# 1_SCH_RP2040.net
KiCad netlist of a schematic drawn in Altium Designer
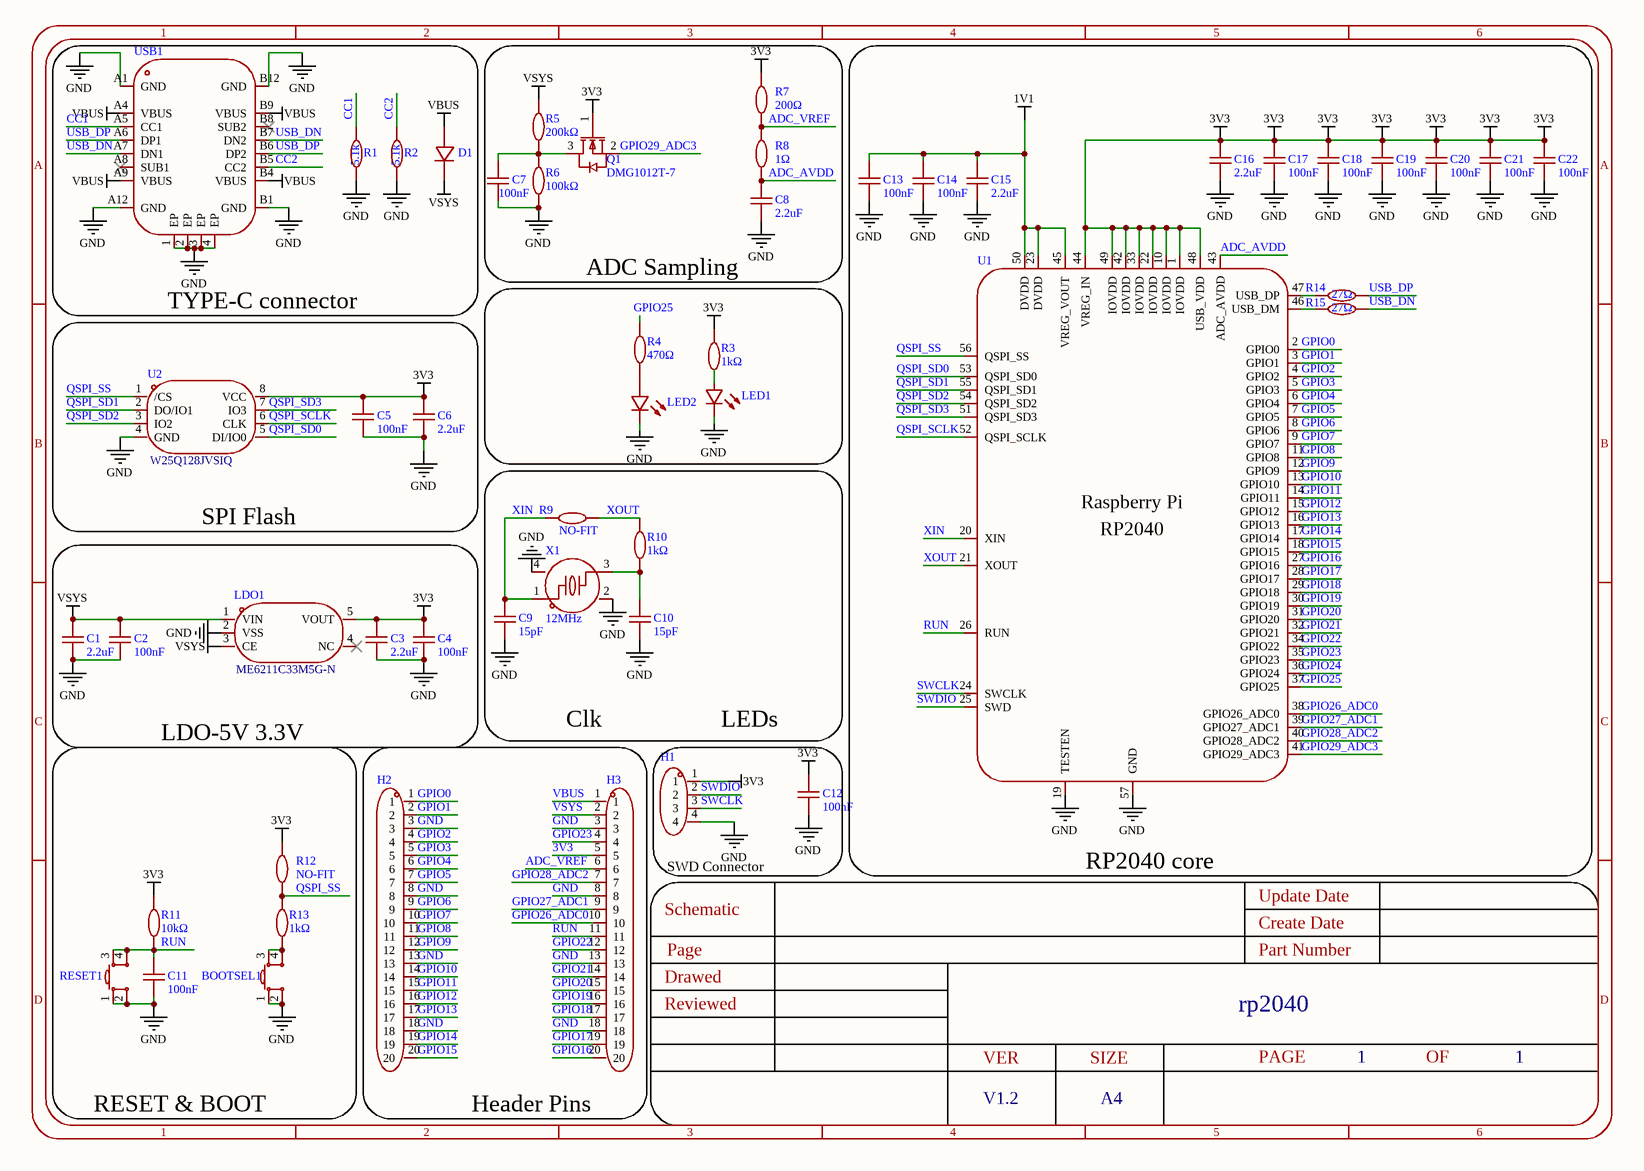
[diagram p0: 1_SCH_RP2040.schdoc]

(export (version "E")
  (design (tool "Eeschema 10.0.6"))
  (components
    (comp (ref "BOOTSEL1")
      (value "PTS815SJK250SMTRLFS")
      (footprint "SW-SMD_4P-L4.2-W3.3-P2.15-LS5.1")
      (fields (field (name "MANUFACTURER") "C&K"))
      (libsource (lib "altium-import") (part "root_1_PTS815SJK250SMTRLFS_"))
    )
    (comp (ref "C1")
      (value "2.2uF")
      (footprint "C0603")
      (fields
        (field (name "MANUFACTURER") "SAMSUNG(三星)")
        (field (name "MANUFACTURER PART") "CL10A225KO8NNNC")
        (field (name "TOLERANCE") "±10%")
      )
      (libsource (lib "altium-import") (part "root_1_CL10A225KO8NNNC_"))
    )
    (comp (ref "C2")
      (value "100nF")
      (footprint "C0603")
      (fields
        (field (name "MANUFACTURER") "FH(风华)")
        (field (name "MANUFACTURER PART") "0603B104K500NT")
        (field (name "TOLERANCE") "±10%")
      )
      (libsource (lib "altium-import") (part "root_1_0603B104K500NT_"))
    )
    (comp (ref "C3")
      (value "2.2uF")
      (footprint "C0603")
      (fields
        (field (name "MANUFACTURER") "SAMSUNG(三星)")
        (field (name "MANUFACTURER PART") "CL10A225KO8NNNC")
        (field (name "TOLERANCE") "±10%")
      )
      (libsource (lib "altium-import") (part "root_1_CL10A225KO8NNNC_"))
    )
    (comp (ref "C4")
      (value "100nF")
      (footprint "C0603")
      (fields
        (field (name "MANUFACTURER") "FH(风华)")
        (field (name "MANUFACTURER PART") "0603B104K500NT")
        (field (name "TOLERANCE") "±10%")
      )
      (libsource (lib "altium-import") (part "root_1_0603B104K500NT_"))
    )
    (comp (ref "C5")
      (value "100nF")
      (footprint "C0603")
      (fields
        (field (name "MANUFACTURER") "FH(风华)")
        (field (name "MANUFACTURER PART") "0603B104K500NT")
        (field (name "TOLERANCE") "±10%")
      )
      (libsource (lib "altium-import") (part "root_1_0603B104K500NT_"))
    )
    (comp (ref "C6")
      (value "2.2uF")
      (footprint "C0603")
      (fields
        (field (name "MANUFACTURER") "SAMSUNG(三星)")
        (field (name "MANUFACTURER PART") "CL10A225KO8NNNC")
        (field (name "TOLERANCE") "±10%")
      )
      (libsource (lib "altium-import") (part "root_1_CL10A225KO8NNNC_"))
    )
    (comp (ref "C7")
      (value "100nF")
      (footprint "C0603")
      (fields
        (field (name "MANUFACTURER") "FH(风华)")
        (field (name "MANUFACTURER PART") "0603B104K500NT")
        (field (name "TOLERANCE") "±10%")
      )
      (libsource (lib "altium-import") (part "root_1_0603B104K500NT_"))
    )
    (comp (ref "C8")
      (value "2.2uF")
      (footprint "C0603")
      (fields
        (field (name "MANUFACTURER") "SAMSUNG(三星)")
        (field (name "MANUFACTURER PART") "CL10A225KO8NNNC")
        (field (name "TOLERANCE") "±10%")
      )
      (libsource (lib "altium-import") (part "root_1_CL10A225KO8NNNC_"))
    )
    (comp (ref "C9")
      (value "15pF")
      (footprint "C0603")
      (fields
        (field (name "MANUFACTURER") "YAGEO(国巨)")
        (field (name "MANUFACTURER PART") "CC0603JRNPO9BN150")
        (field (name "TOLERANCE") "±5%")
      )
      (libsource (lib "altium-import") (part "root_3_CC0603JRNPO9BN150_"))
    )
    (comp (ref "C10")
      (value "15pF")
      (footprint "C0603")
      (fields
        (field (name "MANUFACTURER") "YAGEO(国巨)")
        (field (name "MANUFACTURER PART") "CC0603JRNPO9BN150")
        (field (name "TOLERANCE") "±5%")
      )
      (libsource (lib "altium-import") (part "root_3_CC0603JRNPO9BN150_"))
    )
    (comp (ref "C11")
      (value "100nF")
      (footprint "C0603")
      (fields
        (field (name "MANUFACTURER") "FH(风华)")
        (field (name "MANUFACTURER PART") "0603B104K500NT")
        (field (name "TOLERANCE") "±10%")
      )
      (libsource (lib "altium-import") (part "root_1_0603B104K500NT_"))
    )
    (comp (ref "C12")
      (value "100nF")
      (footprint "C0603")
      (fields
        (field (name "MANUFACTURER") "FH(风华)")
        (field (name "MANUFACTURER PART") "0603B104K500NT")
        (field (name "TOLERANCE") "±10%")
      )
      (libsource (lib "altium-import") (part "root_3_0603B104K500NT_"))
    )
    (comp (ref "C13")
      (value "100nF")
      (footprint "C0603")
      (fields
        (field (name "MANUFACTURER") "FH(风华)")
        (field (name "MANUFACTURER PART") "0603B104K500NT")
        (field (name "TOLERANCE") "±10%")
      )
      (libsource (lib "altium-import") (part "root_3_0603B104K500NT_"))
    )
    (comp (ref "C14")
      (value "100nF")
      (footprint "C0603")
      (fields
        (field (name "MANUFACTURER") "FH(风华)")
        (field (name "MANUFACTURER PART") "0603B104K500NT")
        (field (name "TOLERANCE") "±10%")
      )
      (libsource (lib "altium-import") (part "root_1_0603B104K500NT_"))
    )
    (comp (ref "C15")
      (value "2.2uF")
      (footprint "C0603")
      (fields
        (field (name "MANUFACTURER") "SAMSUNG(三星)")
        (field (name "MANUFACTURER PART") "CL10A225KO8NNNC")
        (field (name "TOLERANCE") "±10%")
      )
      (libsource (lib "altium-import") (part "root_1_CL10A225KO8NNNC_"))
    )
    (comp (ref "C16")
      (value "2.2uF")
      (footprint "C0603")
      (fields
        (field (name "MANUFACTURER") "SAMSUNG(三星)")
        (field (name "MANUFACTURER PART") "CL10A225KO8NNNC")
        (field (name "TOLERANCE") "±10%")
      )
      (libsource (lib "altium-import") (part "root_3_CL10A225KO8NNNC_"))
    )
    (comp (ref "C17")
      (value "100nF")
      (footprint "C0603")
      (fields
        (field (name "MANUFACTURER") "FH(风华)")
        (field (name "MANUFACTURER PART") "0603B104K500NT")
        (field (name "TOLERANCE") "±10%")
      )
      (libsource (lib "altium-import") (part "root_1_0603B104K500NT_"))
    )
    (comp (ref "C18")
      (value "100nF")
      (footprint "C0603")
      (fields
        (field (name "MANUFACTURER") "FH(风华)")
        (field (name "MANUFACTURER PART") "0603B104K500NT")
        (field (name "TOLERANCE") "±10%")
      )
      (libsource (lib "altium-import") (part "root_1_0603B104K500NT_"))
    )
    (comp (ref "C19")
      (value "100nF")
      (footprint "C0603")
      (fields
        (field (name "MANUFACTURER") "FH(风华)")
        (field (name "MANUFACTURER PART") "0603B104K500NT")
        (field (name "TOLERANCE") "±10%")
      )
      (libsource (lib "altium-import") (part "root_1_0603B104K500NT_"))
    )
    (comp (ref "C20")
      (value "100nF")
      (footprint "C0603")
      (fields
        (field (name "MANUFACTURER") "FH(风华)")
        (field (name "MANUFACTURER PART") "0603B104K500NT")
        (field (name "TOLERANCE") "±10%")
      )
      (libsource (lib "altium-import") (part "root_1_0603B104K500NT_"))
    )
    (comp (ref "C21")
      (value "100nF")
      (footprint "C0603")
      (fields
        (field (name "MANUFACTURER") "FH(风华)")
        (field (name "MANUFACTURER PART") "0603B104K500NT")
        (field (name "TOLERANCE") "±10%")
      )
      (libsource (lib "altium-import") (part "root_1_0603B104K500NT_"))
    )
    (comp (ref "C22")
      (value "100nF")
      (footprint "C0603")
      (fields
        (field (name "MANUFACTURER") "FH(风华)")
        (field (name "MANUFACTURER PART") "0603B104K500NT")
        (field (name "TOLERANCE") "±10%")
      )
      (libsource (lib "altium-import") (part "root_1_0603B104K500NT_"))
    )
    (comp (ref "D1")
      (value "1N4007W")
      (footprint "SOD-123FL_L2.7-W1.8-LS3.8-RD")
      (fields (field (name "MANUFACTURER") "晶导微电子"))
      (libsource (lib "altium-import") (part "root_1_1N4007W_C108803_"))
    )
    (comp (ref "H1")
      (value "DZ254W-11-04-65")
      (footprint "HDR-TH_4P-P2.54-H-M-W10.3")
      (fields (field (name "MANUFACTURER") "DEALON(德艺隆)"))
      (libsource (lib "altium-import") (part "root_0_mirrored_DZ254W-11-04-65_"))
    )
    (comp (ref "H2")
      (value "12251120CNG0S115005")
      (footprint "HDR-TH_20P-P2.54-V-M-1")
      (fields (field (name "MANUFACTURER") "JILN(锦凌)"))
      (libsource (lib "altium-import") (part "root_0_mirrored_12251120CNG0S115005_"))
    )
    (comp (ref "H3")
      (value "12251120CNG0S115005")
      (footprint "HDR-TH_20P-P2.54-V-M-1")
      (fields (field (name "MANUFACTURER") "JILN(锦凌)"))
      (libsource (lib "altium-import") (part "root_0_12251120CNG0S115005_"))
    )
    (comp (ref "LDO1")
      (value "ME6211C33M5G-N")
      (footprint "SOT-23-5_L3.0-W1.7-P0.95-LS2.8-BR")
      (fields (field (name "DEVICE") "ME6211C33M5G-N") (field (name "MANUFACTURER") "MICRONE(南京微盟)"))
      (libsource (lib "altium-import") (part "root_0_ME6211C33M5G-N_"))
    )
    (comp (ref "LED1")
      (value "NCD0603R1")
      (footprint "LED0603-RD_RED")
      (fields (field (name "MANUFACTURER") "国星光电"))
      (libsource (lib "altium-import") (part "root_1_mirrored_NCD0603R1_C84263_"))
    )
    (comp (ref "LED2")
      (value "19-217/BHC-ZL1M2RY/3T")
      (footprint "LED0603-R-RD_BLUE")
      (fields (field (name "MANUFACTURER") "EVERLIGHT(亿光)"))
      (libsource (lib "altium-import") (part "root_1_mirrored_19-217/BHC-ZL1M2RY/3T_"))
    )
    (comp (ref "Q1")
      (value "DMG1012T-7")
      (footprint "SOT-523-3_L1.6-W0.8-P1.00-LS1.6-BR")
      (fields (field (name "DEVICE") "DMG1012T-7") (field (name "MANUFACTURER") "DIODES(美台)"))
      (libsource (lib "altium-import") (part "root_3_mirrored_DMG1012T-7_"))
    )
    (comp (ref "R1")
      (value "5.1k")
      (footprint "R0603")
      (fields
        (field (name "MANUFACTURER") "YAGEO(国巨)")
        (field (name "MANUFACTURER PART") "RC0603FR-075K1L")
        (field (name "TOLERANCE") "±1%")
      )
      (libsource (lib "altium-import") (part "root_1_RC0603FR-075K1L_"))
    )
    (comp (ref "R2")
      (value "5.1k")
      (footprint "R0603")
      (fields
        (field (name "MANUFACTURER") "YAGEO(国巨)")
        (field (name "MANUFACTURER PART") "RC0603FR-075K1L")
        (field (name "TOLERANCE") "±1%")
      )
      (libsource (lib "altium-import") (part "root_1_RC0603FR-075K1L_"))
    )
    (comp (ref "R3")
      (value "1kΩ")
      (footprint "R0603")
      (fields
        (field (name "MANUFACTURER") "YAGEO(国巨)")
        (field (name "MANUFACTURER PART") "RC0603FR-071KL")
        (field (name "TOLERANCE") "±1%")
      )
      (libsource (lib "altium-import") (part "root_1_RC0603FR-071KL_"))
    )
    (comp (ref "R4")
      (value "470Ω")
      (footprint "R0603")
      (fields
        (field (name "MANUFACTURER") "YAGEO(国巨)")
        (field (name "MANUFACTURER PART") "RC0603FR-07470RL")
        (field (name "TOLERANCE") "±1%")
      )
      (libsource (lib "altium-import") (part "root_1_RC0603FR-07470RL_"))
    )
    (comp (ref "R5")
      (value "200kΩ")
      (footprint "R0603")
      (fields
        (field (name "MANUFACTURER") "YAGEO(国巨)")
        (field (name "MANUFACTURER PART") "RC0603FR-07200KL")
        (field (name "TOLERANCE") "±1%")
      )
      (libsource (lib "altium-import") (part "root_1_RC0603FR-07200KL_"))
    )
    (comp (ref "R6")
      (value "100kΩ")
      (footprint "R0603")
      (fields
        (field (name "MANUFACTURER") "YAGEO(国巨)")
        (field (name "MANUFACTURER PART") "RC0603FR-07100KL")
        (field (name "TOLERANCE") "±1%")
      )
      (libsource (lib "altium-import") (part "root_1_RC0603FR-07100KL_"))
    )
    (comp (ref "R7")
      (value "200Ω")
      (footprint "R0603")
      (fields
        (field (name "MANUFACTURER") "YAGEO(国巨)")
        (field (name "MANUFACTURER PART") "RC0603FR-07200RL")
        (field (name "TOLERANCE") "±1%")
      )
      (libsource (lib "altium-import") (part "root_1_RC0603FR-07200RL_"))
    )
    (comp (ref "R8")
      (value "1Ω")
      (footprint "R0603")
      (fields
        (field (name "MANUFACTURER") "YAGEO(国巨)")
        (field (name "MANUFACTURER PART") "RC0603FR-071RL")
        (field (name "TOLERANCE") "±1%")
      )
      (libsource (lib "altium-import") (part "root_1_RC0603FR-071RL_"))
    )
    (comp (ref "R9")
      (value "NO-FIT")
      (footprint "R0603")
      (libsource (lib "altium-import") (part "root_0_RC0603FR-071KL_"))
    )
    (comp (ref "R10")
      (value "1kΩ")
      (footprint "R0603")
      (fields
        (field (name "MANUFACTURER") "YAGEO(国巨)")
        (field (name "MANUFACTURER PART") "RC0603FR-071KL")
        (field (name "TOLERANCE") "±1%")
      )
      (libsource (lib "altium-import") (part "root_1_RC0603FR-071KL_"))
    )
    (comp (ref "R11")
      (value "10kΩ")
      (footprint "R0603")
      (fields
        (field (name "MANUFACTURER") "UNI-ROYAL(厚声)")
        (field (name "MANUFACTURER PART") "0603WAF1002T5E")
        (field (name "TOLERANCE") "±1%")
      )
      (libsource (lib "altium-import") (part "root_1_0603WAF1002T5E_"))
    )
    (comp (ref "R12")
      (value "NO-FIT")
      (footprint "R0603")
      (libsource (lib "altium-import") (part "root_3_RC0603FR-071KL_"))
    )
    (comp (ref "R13")
      (value "1kΩ")
      (footprint "R0603")
      (fields
        (field (name "MANUFACTURER") "YAGEO(国巨)")
        (field (name "MANUFACTURER PART") "RC0603FR-071KL")
        (field (name "TOLERANCE") "±1%")
      )
      (libsource (lib "altium-import") (part "root_1_RC0603FR-071KL_"))
    )
    (comp (ref "R14")
      (value "27Ω")
      (footprint "R0603")
      (fields
        (field (name "MANUFACTURER") "UNI-ROYAL(厚声)")
        (field (name "MANUFACTURER PART") "0603WAF270JT5E")
        (field (name "TOLERANCE") "±1%")
      )
      (libsource (lib "altium-import") (part "root_0_0603WAF270JT5E_"))
    )
    (comp (ref "R15")
      (value "27Ω")
      (footprint "R0603")
      (fields
        (field (name "MANUFACTURER") "UNI-ROYAL(厚声)")
        (field (name "MANUFACTURER PART") "0603WAF270JT5E")
        (field (name "TOLERANCE") "±1%")
      )
      (libsource (lib "altium-import") (part "root_0_0603WAF270JT5E_"))
    )
    (comp (ref "RESET1")
      (value "PTS815SJK250SMTRLFS")
      (footprint "SW-SMD_4P-L4.2-W3.3-P2.15-LS5.1")
      (fields (field (name "MANUFACTURER") "C&K"))
      (libsource (lib "altium-import") (part "root_1_PTS815SJK250SMTRLFS_"))
    )
    (comp (ref "U1")
      (value "RP2040")
      (footprint "LQFN-56_L7.0-W7.0-P0.4-EP")
      (fields (field (name "MANUFACTURER") "Raspberry Pi(树莓派)"))
      (libsource (lib "altium-import") (part "root_0_RP2040_C2040_"))
    )
    (comp (ref "U2")
      (value "W25Q128JVSIQ")
      (footprint "SOIC-8_L5.3-W5.3-P1.27-LS8.0-BL")
      (fields (field (name "DEVICE") "W25Q128JVSIQ") (field (name "MANUFACTURER") "WINBOND(华邦)"))
      (libsource (lib "altium-import") (part "root_0_W25Q128JVSIQ_"))
    )
    (comp (ref "USB1")
      (value "KH-TYPE-C-16P")
      (footprint "USB-C-SMD_KH-TYPE-C-16P")
      (fields (field (name "MANUFACTURER") "kinghelm(金航标)"))
      (libsource (lib "altium-import") (part "root_0_KH-TYPE-C-16P_"))
    )
    (comp (ref "X1")
      (value "12MHz")
      (footprint "CRYSTAL-SMD_4P-L3.2-W2.5-BL")
      (fields
        (field (name "MANUFACTURER") "HCI(杭晶)")
        (field (name "MANUFACTURER PART") "XC32M4-12.000-F10NNFT")
      )
      (libsource (lib "altium-import") (part "root_0_XC32M4-12.000-F10NNFT_"))
    )
  )
  (nets
    (net (code "1") (name "/ADC_AVDD") (class "Default")
      (node (ref "C8") (pin "2") (pinfunction "2_2") (pintype "passive"))
      (node (ref "R8") (pin "1") (pinfunction "1_1") (pintype "passive"))
      (node (ref "U1") (pin "43") (pinfunction "ADC_AVDD_43") (pintype "passive"))
    )
    (net (code "2") (name "/ADC_VREF") (class "Default")
      (node (ref "H3") (pin "6") (pinfunction "6_6") (pintype "passive"))
      (node (ref "R7") (pin "1") (pinfunction "1_1") (pintype "passive"))
      (node (ref "R8") (pin "2") (pinfunction "2_2") (pintype "passive"))
    )
    (net (code "3") (name "/CC1") (class "Default")
      (node (ref "R1") (pin "2") (pinfunction "2_2") (pintype "passive"))
      (node (ref "USB1") (pin "A5") (pinfunction "CC1_A5") (pintype "passive"))
    )
    (net (code "4") (name "/CC2") (class "Default")
      (node (ref "R2") (pin "2") (pinfunction "2_2") (pintype "passive"))
      (node (ref "USB1") (pin "B5") (pinfunction "CC2_B5") (pintype "passive"))
    )
    (net (code "5") (name "/GPIO0") (class "Default")
      (node (ref "H2") (pin "1") (pinfunction "1_1") (pintype "passive"))
      (node (ref "U1") (pin "2") (pinfunction "GPIO0_2") (pintype "passive"))
    )
    (net (code "6") (name "/GPIO1") (class "Default")
      (node (ref "H2") (pin "2") (pinfunction "2_2") (pintype "passive"))
      (node (ref "U1") (pin "3") (pinfunction "GPIO1_3") (pintype "passive"))
    )
    (net (code "7") (name "/GPIO2") (class "Default")
      (node (ref "H2") (pin "4") (pinfunction "4_4") (pintype "passive"))
      (node (ref "U1") (pin "4") (pinfunction "GPIO2_4") (pintype "passive"))
    )
    (net (code "8") (name "/GPIO3") (class "Default")
      (node (ref "H2") (pin "5") (pinfunction "5_5") (pintype "passive"))
      (node (ref "U1") (pin "5") (pinfunction "GPIO3_5") (pintype "passive"))
    )
    (net (code "9") (name "/GPIO4") (class "Default")
      (node (ref "H2") (pin "6") (pinfunction "6_6") (pintype "passive"))
      (node (ref "U1") (pin "6") (pinfunction "GPIO4_6") (pintype "passive"))
    )
    (net (code "10") (name "/GPIO5") (class "Default")
      (node (ref "H2") (pin "7") (pinfunction "7_7") (pintype "passive"))
      (node (ref "U1") (pin "7") (pinfunction "GPIO5_7") (pintype "passive"))
    )
    (net (code "11") (name "/GPIO6") (class "Default")
      (node (ref "H2") (pin "9") (pinfunction "9_9") (pintype "passive"))
      (node (ref "U1") (pin "8") (pinfunction "GPIO6_8") (pintype "passive"))
    )
    (net (code "12") (name "/GPIO7") (class "Default")
      (node (ref "H2") (pin "10") (pinfunction "10_10") (pintype "passive"))
      (node (ref "U1") (pin "9") (pinfunction "GPIO7_9") (pintype "passive"))
    )
    (net (code "13") (name "/GPIO8") (class "Default")
      (node (ref "H2") (pin "11") (pinfunction "11_11") (pintype "passive"))
      (node (ref "U1") (pin "11") (pinfunction "GPIO8_11") (pintype "passive"))
    )
    (net (code "14") (name "/GPIO9") (class "Default")
      (node (ref "H2") (pin "12") (pinfunction "12_12") (pintype "passive"))
      (node (ref "U1") (pin "12") (pinfunction "GPIO9_12") (pintype "passive"))
    )
    (net (code "15") (name "/GPIO10") (class "Default")
      (node (ref "H2") (pin "14") (pinfunction "14_14") (pintype "passive"))
      (node (ref "U1") (pin "13") (pinfunction "GPIO10_13") (pintype "passive"))
    )
    (net (code "16") (name "/GPIO11") (class "Default")
      (node (ref "H2") (pin "15") (pinfunction "15_15") (pintype "passive"))
      (node (ref "U1") (pin "14") (pinfunction "GPIO11_14") (pintype "passive"))
    )
    (net (code "17") (name "/GPIO12") (class "Default")
      (node (ref "H2") (pin "16") (pinfunction "16_16") (pintype "passive"))
      (node (ref "U1") (pin "15") (pinfunction "GPIO12_15") (pintype "passive"))
    )
    (net (code "18") (name "/GPIO13") (class "Default")
      (node (ref "H2") (pin "17") (pinfunction "17_17") (pintype "passive"))
      (node (ref "U1") (pin "16") (pinfunction "GPIO13_16") (pintype "passive"))
    )
    (net (code "19") (name "/GPIO14") (class "Default")
      (node (ref "H2") (pin "19") (pinfunction "19_19") (pintype "passive"))
      (node (ref "U1") (pin "17") (pinfunction "GPIO14_17") (pintype "passive"))
    )
    (net (code "20") (name "/GPIO15") (class "Default")
      (node (ref "H2") (pin "20") (pinfunction "20_20") (pintype "passive"))
      (node (ref "U1") (pin "18") (pinfunction "GPIO15_18") (pintype "passive"))
    )
    (net (code "21") (name "/GPIO16") (class "Default")
      (node (ref "H3") (pin "20") (pinfunction "20_20") (pintype "passive"))
      (node (ref "U1") (pin "27") (pinfunction "GPIO16_27") (pintype "passive"))
    )
    (net (code "22") (name "/GPIO17") (class "Default")
      (node (ref "H3") (pin "19") (pinfunction "19_19") (pintype "passive"))
      (node (ref "U1") (pin "28") (pinfunction "GPIO17_28") (pintype "passive"))
    )
    (net (code "23") (name "/GPIO18") (class "Default")
      (node (ref "H3") (pin "17") (pinfunction "17_17") (pintype "passive"))
      (node (ref "U1") (pin "29") (pinfunction "GPIO18_29") (pintype "passive"))
    )
    (net (code "24") (name "/GPIO19") (class "Default")
      (node (ref "H3") (pin "16") (pinfunction "16_16") (pintype "passive"))
      (node (ref "U1") (pin "30") (pinfunction "GPIO19_30") (pintype "passive"))
    )
    (net (code "25") (name "/GPIO20") (class "Default")
      (node (ref "H3") (pin "15") (pinfunction "15_15") (pintype "passive"))
      (node (ref "U1") (pin "31") (pinfunction "GPIO20_31") (pintype "passive"))
    )
    (net (code "26") (name "/GPIO21") (class "Default")
      (node (ref "H3") (pin "14") (pinfunction "14_14") (pintype "passive"))
      (node (ref "U1") (pin "32") (pinfunction "GPIO21_32") (pintype "passive"))
    )
    (net (code "27") (name "/GPIO22") (class "Default")
      (node (ref "H3") (pin "12") (pinfunction "12_12") (pintype "passive"))
      (node (ref "U1") (pin "34") (pinfunction "GPIO22_34") (pintype "passive"))
    )
    (net (code "28") (name "/GPIO23") (class "Default")
      (node (ref "H3") (pin "4") (pinfunction "4_4") (pintype "passive"))
      (node (ref "U1") (pin "35") (pinfunction "GPIO23_35") (pintype "passive"))
    )
    (net (code "29") (name "/GPIO24") (class "Default")
      (node (ref "U1") (pin "36") (pinfunction "GPIO24_36") (pintype "passive"))
    )
    (net (code "30") (name "/GPIO25") (class "Default")
      (node (ref "U1") (pin "37") (pinfunction "GPIO25_37") (pintype "passive"))
    )
    (net (code "31") (name "/GPIO26_ADC0") (class "Default")
      (node (ref "H3") (pin "10") (pinfunction "10_10") (pintype "passive"))
      (node (ref "U1") (pin "38") (pinfunction "GPIO26_ADC0_38") (pintype "passive"))
    )
    (net (code "32") (name "/GPIO27_ADC1") (class "Default")
      (node (ref "H3") (pin "9") (pinfunction "9_9") (pintype "passive"))
      (node (ref "U1") (pin "39") (pinfunction "GPIO27_ADC1_39") (pintype "passive"))
    )
    (net (code "33") (name "/GPIO28_ADC2") (class "Default")
      (node (ref "H3") (pin "7") (pinfunction "7_7") (pintype "passive"))
      (node (ref "U1") (pin "40") (pinfunction "GPIO28_ADC2_40") (pintype "passive"))
    )
    (net (code "34") (name "/GPIO29_ADC3") (class "Default")
      (node (ref "Q1") (pin "2") (pinfunction "S_2") (pintype "passive"))
      (node (ref "U1") (pin "41") (pinfunction "GPIO29_ADC3_41") (pintype "passive"))
    )
    (net (code "35") (name "/QSPI_SCLK") (class "Default")
      (node (ref "U1") (pin "52") (pinfunction "QSPI_SCLK_52") (pintype "passive"))
      (node (ref "U2") (pin "6") (pinfunction "CLK_6") (pintype "passive"))
    )
    (net (code "36") (name "/QSPI_SD0") (class "Default")
      (node (ref "U1") (pin "53") (pinfunction "QSPI_SD0_53") (pintype "passive"))
      (node (ref "U2") (pin "5") (pinfunction "DI/IO0_5") (pintype "passive"))
    )
    (net (code "37") (name "/QSPI_SD1") (class "Default")
      (node (ref "U1") (pin "55") (pinfunction "QSPI_SD1_55") (pintype "passive"))
      (node (ref "U2") (pin "2") (pinfunction "DO/IO1_2") (pintype "passive"))
    )
    (net (code "38") (name "/QSPI_SD2") (class "Default")
      (node (ref "U1") (pin "54") (pinfunction "QSPI_SD2_54") (pintype "passive"))
      (node (ref "U2") (pin "3") (pinfunction "IO2_3") (pintype "passive"))
    )
    (net (code "39") (name "/QSPI_SD3") (class "Default")
      (node (ref "U1") (pin "51") (pinfunction "QSPI_SD3_51") (pintype "passive"))
      (node (ref "U2") (pin "7") (pinfunction "IO3_7") (pintype "passive"))
    )
    (net (code "40") (name "/QSPI_SS") (class "Default")
      (node (ref "R12") (pin "2") (pinfunction "2_2") (pintype "passive"))
      (node (ref "R13") (pin "2") (pinfunction "2_2") (pintype "passive"))
      (node (ref "U1") (pin "56") (pinfunction "QSPI_SS_56") (pintype "passive"))
      (node (ref "U2") (pin "1") (pinfunction "/CS_1") (pintype "passive"))
    )
    (net (code "41") (name "/RUN") (class "Default")
      (node (ref "C11") (pin "2") (pinfunction "2_2") (pintype "passive"))
      (node (ref "H3") (pin "11") (pinfunction "11_11") (pintype "passive"))
      (node (ref "R11") (pin "1") (pinfunction "1_1") (pintype "passive"))
      (node (ref "RESET1") (pin "3") (pinfunction "3_3") (pintype "passive"))
      (node (ref "RESET1") (pin "4") (pinfunction "4_4") (pintype "passive"))
      (node (ref "U1") (pin "26") (pinfunction "RUN_26") (pintype "passive"))
    )
    (net (code "42") (name "/SWCLK") (class "Default")
      (node (ref "H1") (pin "3") (pinfunction "3_3") (pintype "passive"))
      (node (ref "U1") (pin "24") (pinfunction "SWCLK_24") (pintype "passive"))
    )
    (net (code "43") (name "/SWDIO") (class "Default")
      (node (ref "H1") (pin "2") (pinfunction "2_2") (pintype "passive"))
      (node (ref "U1") (pin "25") (pinfunction "SWD_25") (pintype "passive"))
    )
    (net (code "44") (name "/USB_DN") (class "Default")
      (node (ref "R15") (pin "2") (pinfunction "2_2") (pintype "passive"))
      (node (ref "USB1") (pin "A7") (pinfunction "DN1_A7") (pintype "passive"))
      (node (ref "USB1") (pin "B7") (pinfunction "DN2_B7") (pintype "passive"))
    )
    (net (code "45") (name "/USB_DP") (class "Default")
      (node (ref "R14") (pin "2") (pinfunction "2_2") (pintype "passive"))
      (node (ref "USB1") (pin "A6") (pinfunction "DP1_A6") (pintype "passive"))
      (node (ref "USB1") (pin "B6") (pinfunction "DP2_B6") (pintype "passive"))
    )
    (net (code "46") (name "/XIN") (class "Default")
      (node (ref "C9") (pin "1") (pinfunction "1_1") (pintype "passive"))
      (node (ref "R9") (pin "1") (pinfunction "1_1") (pintype "passive"))
      (node (ref "U1") (pin "20") (pinfunction "XIN_20") (pintype "passive"))
      (node (ref "X1") (pin "1") (pinfunction "1_1") (pintype "passive"))
    )
    (net (code "47") (name "/XOUT") (class "Default")
      (node (ref "R10") (pin "2") (pinfunction "2_2") (pintype "passive"))
      (node (ref "R9") (pin "2") (pinfunction "2_2") (pintype "passive"))
      (node (ref "U1") (pin "21") (pinfunction "XOUT_21") (pintype "passive"))
    )
    (net (code "48") (name "1V1") (class "Default")
      (node (ref "C13") (pin "1") (pinfunction "1_1") (pintype "passive"))
      (node (ref "C14") (pin "2") (pinfunction "2_2") (pintype "passive"))
      (node (ref "C15") (pin "2") (pinfunction "2_2") (pintype "passive"))
      (node (ref "U1") (pin "23") (pinfunction "DVDD_23") (pintype "passive"))
      (node (ref "U1") (pin "45") (pinfunction "VREG_VOUT_45") (pintype "passive"))
      (node (ref "U1") (pin "50") (pinfunction "DVDD_50") (pintype "passive"))
    )
    (net (code "49") (name "3V3") (class "Default")
      (node (ref "C12") (pin "1") (pinfunction "1_1") (pintype "passive"))
      (node (ref "C16") (pin "1") (pinfunction "1_1") (pintype "passive"))
      (node (ref "C17") (pin "2") (pinfunction "2_2") (pintype "passive"))
      (node (ref "C18") (pin "2") (pinfunction "2_2") (pintype "passive"))
      (node (ref "C19") (pin "2") (pinfunction "2_2") (pintype "passive"))
      (node (ref "C20") (pin "2") (pinfunction "2_2") (pintype "passive"))
      (node (ref "C21") (pin "2") (pinfunction "2_2") (pintype "passive"))
      (node (ref "C22") (pin "2") (pinfunction "2_2") (pintype "passive"))
      (node (ref "C3") (pin "2") (pinfunction "2_2") (pintype "passive"))
      (node (ref "C4") (pin "2") (pinfunction "2_2") (pintype "passive"))
      (node (ref "C5") (pin "2") (pinfunction "2_2") (pintype "passive"))
      (node (ref "C6") (pin "2") (pinfunction "2_2") (pintype "passive"))
      (node (ref "H1") (pin "1") (pinfunction "1_1") (pintype "passive"))
      (node (ref "H3") (pin "5") (pinfunction "5_5") (pintype "passive"))
      (node (ref "LDO1") (pin "5") (pinfunction "VOUT_5") (pintype "passive"))
      (node (ref "Q1") (pin "1") (pinfunction "G_1") (pintype "passive"))
      (node (ref "R11") (pin "2") (pinfunction "2_2") (pintype "passive"))
      (node (ref "R12") (pin "1") (pinfunction "1_1") (pintype "passive"))
      (node (ref "R3") (pin "2") (pinfunction "2_2") (pintype "passive"))
      (node (ref "R7") (pin "2") (pinfunction "2_2") (pintype "passive"))
      (node (ref "U1") (pin "1") (pinfunction "IOVDD_1") (pintype "passive"))
      (node (ref "U1") (pin "10") (pinfunction "IOVDD_10") (pintype "passive"))
      (node (ref "U1") (pin "22") (pinfunction "IOVDD_22") (pintype "passive"))
      (node (ref "U1") (pin "33") (pinfunction "IOVDD_33") (pintype "passive"))
      (node (ref "U1") (pin "42") (pinfunction "IOVDD_42") (pintype "passive"))
      (node (ref "U1") (pin "44") (pinfunction "VREG_IN_44") (pintype "passive"))
      (node (ref "U1") (pin "48") (pinfunction "USB_VDD_48") (pintype "passive"))
      (node (ref "U1") (pin "49") (pinfunction "IOVDD_49") (pintype "passive"))
      (node (ref "U2") (pin "8") (pinfunction "VCC_8") (pintype "passive"))
    )
    (net (code "50") (name "GND") (class "Default")
      (node (ref "BOOTSEL1") (pin "1") (pinfunction "1_1") (pintype "passive"))
      (node (ref "BOOTSEL1") (pin "2") (pinfunction "2_2") (pintype "passive"))
      (node (ref "C1") (pin "1") (pinfunction "1_1") (pintype "passive"))
      (node (ref "C10") (pin "2") (pinfunction "2_2") (pintype "passive"))
      (node (ref "C11") (pin "1") (pinfunction "1_1") (pintype "passive"))
      (node (ref "C12") (pin "2") (pinfunction "2_2") (pintype "passive"))
      (node (ref "C13") (pin "2") (pinfunction "2_2") (pintype "passive"))
      (node (ref "C14") (pin "1") (pinfunction "1_1") (pintype "passive"))
      (node (ref "C15") (pin "1") (pinfunction "1_1") (pintype "passive"))
      (node (ref "C16") (pin "2") (pinfunction "2_2") (pintype "passive"))
      (node (ref "C17") (pin "1") (pinfunction "1_1") (pintype "passive"))
      (node (ref "C18") (pin "1") (pinfunction "1_1") (pintype "passive"))
      (node (ref "C19") (pin "1") (pinfunction "1_1") (pintype "passive"))
      (node (ref "C2") (pin "1") (pinfunction "1_1") (pintype "passive"))
      (node (ref "C20") (pin "1") (pinfunction "1_1") (pintype "passive"))
      (node (ref "C21") (pin "1") (pinfunction "1_1") (pintype "passive"))
      (node (ref "C22") (pin "1") (pinfunction "1_1") (pintype "passive"))
      (node (ref "C3") (pin "1") (pinfunction "1_1") (pintype "passive"))
      (node (ref "C4") (pin "1") (pinfunction "1_1") (pintype "passive"))
      (node (ref "C5") (pin "1") (pinfunction "1_1") (pintype "passive"))
      (node (ref "C6") (pin "1") (pinfunction "1_1") (pintype "passive"))
      (node (ref "C7") (pin "1") (pinfunction "1_1") (pintype "passive"))
      (node (ref "C8") (pin "1") (pinfunction "1_1") (pintype "passive"))
      (node (ref "C9") (pin "2") (pinfunction "2_2") (pintype "passive"))
      (node (ref "H1") (pin "4") (pinfunction "4_4") (pintype "passive"))
      (node (ref "H2") (pin "13") (pinfunction "13_13") (pintype "passive"))
      (node (ref "H2") (pin "18") (pinfunction "18_18") (pintype "passive"))
      (node (ref "H2") (pin "3") (pinfunction "3_3") (pintype "passive"))
      (node (ref "H2") (pin "8") (pinfunction "8_8") (pintype "passive"))
      (node (ref "H3") (pin "13") (pinfunction "13_13") (pintype "passive"))
      (node (ref "H3") (pin "18") (pinfunction "18_18") (pintype "passive"))
      (node (ref "H3") (pin "3") (pinfunction "3_3") (pintype "passive"))
      (node (ref "H3") (pin "8") (pinfunction "8_8") (pintype "passive"))
      (node (ref "LDO1") (pin "2") (pinfunction "VSS_2") (pintype "passive"))
      (node (ref "LED1") (pin "1") (pinfunction "K_1") (pintype "passive"))
      (node (ref "LED2") (pin "1") (pinfunction "C_1") (pintype "passive"))
      (node (ref "R1") (pin "1") (pinfunction "1_1") (pintype "passive"))
      (node (ref "R2") (pin "1") (pinfunction "1_1") (pintype "passive"))
      (node (ref "R6") (pin "1") (pinfunction "1_1") (pintype "passive"))
      (node (ref "RESET1") (pin "1") (pinfunction "1_1") (pintype "passive"))
      (node (ref "RESET1") (pin "2") (pinfunction "2_2") (pintype "passive"))
      (node (ref "U1") (pin "19") (pinfunction "TESTEN_19") (pintype "passive"))
      (node (ref "U1") (pin "57") (pinfunction "GND_57") (pintype "passive"))
      (node (ref "U2") (pin "4") (pinfunction "GND_4") (pintype "passive"))
      (node (ref "USB1") (pin "1") (pinfunction "EP_1") (pintype "passive"))
      (node (ref "USB1") (pin "2") (pinfunction "EP_2") (pintype "passive"))
      (node (ref "USB1") (pin "3") (pinfunction "EP_3") (pintype "passive"))
      (node (ref "USB1") (pin "4") (pinfunction "EP_4") (pintype "passive"))
      (node (ref "USB1") (pin "A1") (pinfunction "GND_A1") (pintype "passive"))
      (node (ref "USB1") (pin "A12") (pinfunction "GND_A12") (pintype "passive"))
      (node (ref "USB1") (pin "B1") (pinfunction "GND_B1") (pintype "passive"))
      (node (ref "USB1") (pin "B12") (pinfunction "GND_B12") (pintype "passive"))
      (node (ref "X1") (pin "2") (pinfunction "GND_2") (pintype "passive"))
      (node (ref "X1") (pin "4") (pinfunction "GND_4") (pintype "passive"))
    )
    (net (code "51") (name "Net-(BOOTSEL1-Pad3)") (class "Default")
      (node (ref "BOOTSEL1") (pin "3") (pinfunction "3_3") (pintype "passive"))
      (node (ref "BOOTSEL1") (pin "4") (pinfunction "4_4") (pintype "passive"))
      (node (ref "R13") (pin "1") (pinfunction "1_1") (pintype "passive"))
    )
    (net (code "52") (name "Net-(C10-Pad1)") (class "Default")
      (node (ref "C10") (pin "1") (pinfunction "1_1") (pintype "passive"))
      (node (ref "R10") (pin "1") (pinfunction "1_1") (pintype "passive"))
      (node (ref "X1") (pin "3") (pinfunction "3_3") (pintype "passive"))
    )
    (net (code "53") (name "Net-(LED1-A)") (class "Default")
      (node (ref "LED1") (pin "2") (pinfunction "A_2") (pintype "passive"))
      (node (ref "R3") (pin "1") (pinfunction "1_1") (pintype "passive"))
    )
    (net (code "54") (name "Net-(LED2-A)") (class "Default")
      (node (ref "LED2") (pin "2") (pinfunction "A_2") (pintype "passive"))
      (node (ref "R4") (pin "1") (pinfunction "1_1") (pintype "passive"))
    )
    (net (code "55") (name "Net-(Q1-D)") (class "Default")
      (node (ref "C7") (pin "2") (pinfunction "2_2") (pintype "passive"))
      (node (ref "Q1") (pin "3") (pinfunction "D_3") (pintype "passive"))
      (node (ref "R5") (pin "1") (pinfunction "1_1") (pintype "passive"))
      (node (ref "R6") (pin "2") (pinfunction "2_2") (pintype "passive"))
    )
    (net (code "56") (name "Net-(U1-USB_DM)") (class "Default")
      (node (ref "R15") (pin "1") (pinfunction "1_1") (pintype "passive"))
      (node (ref "U1") (pin "46") (pinfunction "USB_DM_46") (pintype "passive"))
    )
    (net (code "57") (name "Net-(U1-USB_DP)") (class "Default")
      (node (ref "R14") (pin "1") (pinfunction "1_1") (pintype "passive"))
      (node (ref "U1") (pin "47") (pinfunction "USB_DP_47") (pintype "passive"))
    )
    (net (code "58") (name "VBUS") (class "Default")
      (node (ref "D1") (pin "2") (pinfunction "A_2") (pintype "passive"))
      (node (ref "H3") (pin "1") (pinfunction "1_1") (pintype "passive"))
      (node (ref "USB1") (pin "A4") (pinfunction "VBUS_A4") (pintype "passive"))
      (node (ref "USB1") (pin "A9") (pinfunction "VBUS_A9") (pintype "passive"))
      (node (ref "USB1") (pin "B4") (pinfunction "VBUS_B4") (pintype "passive"))
      (node (ref "USB1") (pin "B9") (pinfunction "VBUS_B9") (pintype "passive"))
    )
    (net (code "59") (name "VSYS") (class "Default")
      (node (ref "C1") (pin "2") (pinfunction "2_2") (pintype "passive"))
      (node (ref "C2") (pin "2") (pinfunction "2_2") (pintype "passive"))
      (node (ref "D1") (pin "1") (pinfunction "K_1") (pintype "passive"))
      (node (ref "H3") (pin "2") (pinfunction "2_2") (pintype "passive"))
      (node (ref "LDO1") (pin "1") (pinfunction "VIN_1") (pintype "passive"))
      (node (ref "LDO1") (pin "3") (pinfunction "CE_3") (pintype "passive"))
      (node (ref "R5") (pin "2") (pinfunction "2_2") (pintype "passive"))
    )
    (net (code "60") (name "unconnected-(LDO1-NC-Pad4)") (class "Default")
      (node (ref "LDO1") (pin "4") (pinfunction "NC_4") (pintype "passive+no_connect"))
    )
    (net (code "61") (name "unconnected-(R4-Pad2)") (class "Default")
      (node (ref "R4") (pin "2") (pinfunction "2_2") (pintype "passive"))
    )
    (net (code "62") (name "unconnected-(USB1-SUB1-PadA8)") (class "Default")
      (node (ref "USB1") (pin "A8") (pinfunction "SUB1_A8") (pintype "passive+no_connect"))
    )
    (net (code "63") (name "unconnected-(USB1-SUB2-PadB8)") (class "Default")
      (node (ref "USB1") (pin "B8") (pinfunction "SUB2_B8") (pintype "passive+no_connect"))
    )
  )
)
